# Input_connector_12ch.net
KiCad netlist of a schematic drawn in Altium Designer
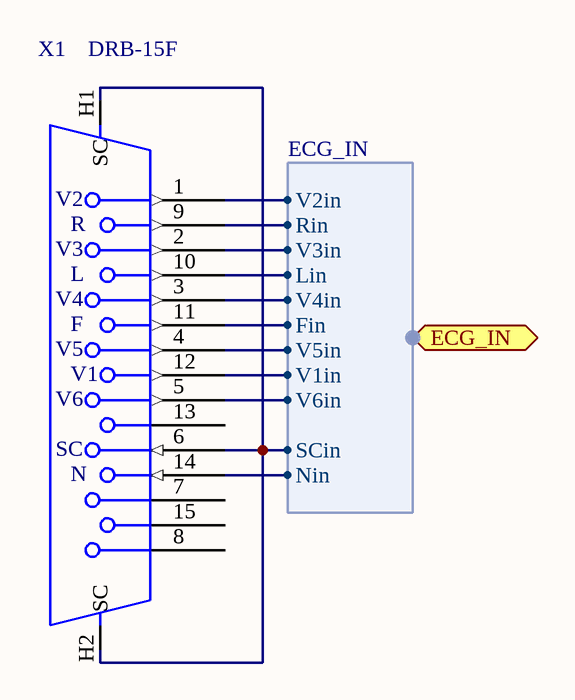
[diagram p0: Input connector 12ch.SchDoc]

(export (version "E")
  (design (tool "Eeschema 10.0.6"))
  (components
    (comp (ref "X1")
      (value "DRB-15F")
      (footprint "DRB-15F")
      (libsource (lib "My_lib") (part "ECG Cable DRB-15F"))
    )
  )
  (nets
    (net (code "2") (name "/Fin") (class "Default")
      (node (ref "X1") (pin "11") (pinfunction "11_11") (pintype "output"))
    )
    (net (code "3") (name "/Lin") (class "Default")
      (node (ref "X1") (pin "10") (pinfunction "10_10") (pintype "output"))
    )
    (net (code "4") (name "/Nin") (class "Default")
      (node (ref "X1") (pin "14") (pinfunction "14_14") (pintype "input"))
    )
    (net (code "5") (name "/Rin") (class "Default")
      (node (ref "X1") (pin "9") (pinfunction "9_9") (pintype "output"))
    )
    (net (code "6") (name "/SCin") (class "Default")
      (node (ref "X1") (pin "6") (pinfunction "6_6") (pintype "input"))
      (node (ref "X1") (pin "H1") (pinfunction "SC_H1") (pintype "passive"))
      (node (ref "X1") (pin "H2") (pinfunction "SC_H2") (pintype "passive"))
    )
    (net (code "7") (name "/V1in") (class "Default")
      (node (ref "X1") (pin "12") (pinfunction "12_12") (pintype "output"))
    )
    (net (code "8") (name "/V2in") (class "Default")
      (node (ref "X1") (pin "1") (pinfunction "1_1") (pintype "output"))
    )
    (net (code "9") (name "/V3in") (class "Default")
      (node (ref "X1") (pin "2") (pinfunction "2_2") (pintype "output"))
    )
    (net (code "10") (name "/V4in") (class "Default")
      (node (ref "X1") (pin "3") (pinfunction "3_3") (pintype "output"))
    )
    (net (code "11") (name "/V5in") (class "Default")
      (node (ref "X1") (pin "4") (pinfunction "4_4") (pintype "output"))
    )
    (net (code "12") (name "/V6in") (class "Default")
      (node (ref "X1") (pin "5") (pinfunction "5_5") (pintype "output"))
    )
    (net (code "14") (name "unconnected-(X1-Pad7)") (class "Default")
      (node (ref "X1") (pin "7") (pinfunction "7_7") (pintype "passive"))
    )
    (net (code "15") (name "unconnected-(X1-Pad8)") (class "Default")
      (node (ref "X1") (pin "8") (pinfunction "8_8") (pintype "passive"))
    )
    (net (code "16") (name "unconnected-(X1-Pad13)") (class "Default")
      (node (ref "X1") (pin "13") (pinfunction "13_13") (pintype "passive"))
    )
    (net (code "17") (name "unconnected-(X1-Pad15)") (class "Default")
      (node (ref "X1") (pin "15") (pinfunction "15_15") (pintype "passive"))
    )
  )
)
